# harp_expander_magnetic_encoder_v1_0.net
KiCad netlist of a schematic drawn in EAGLE
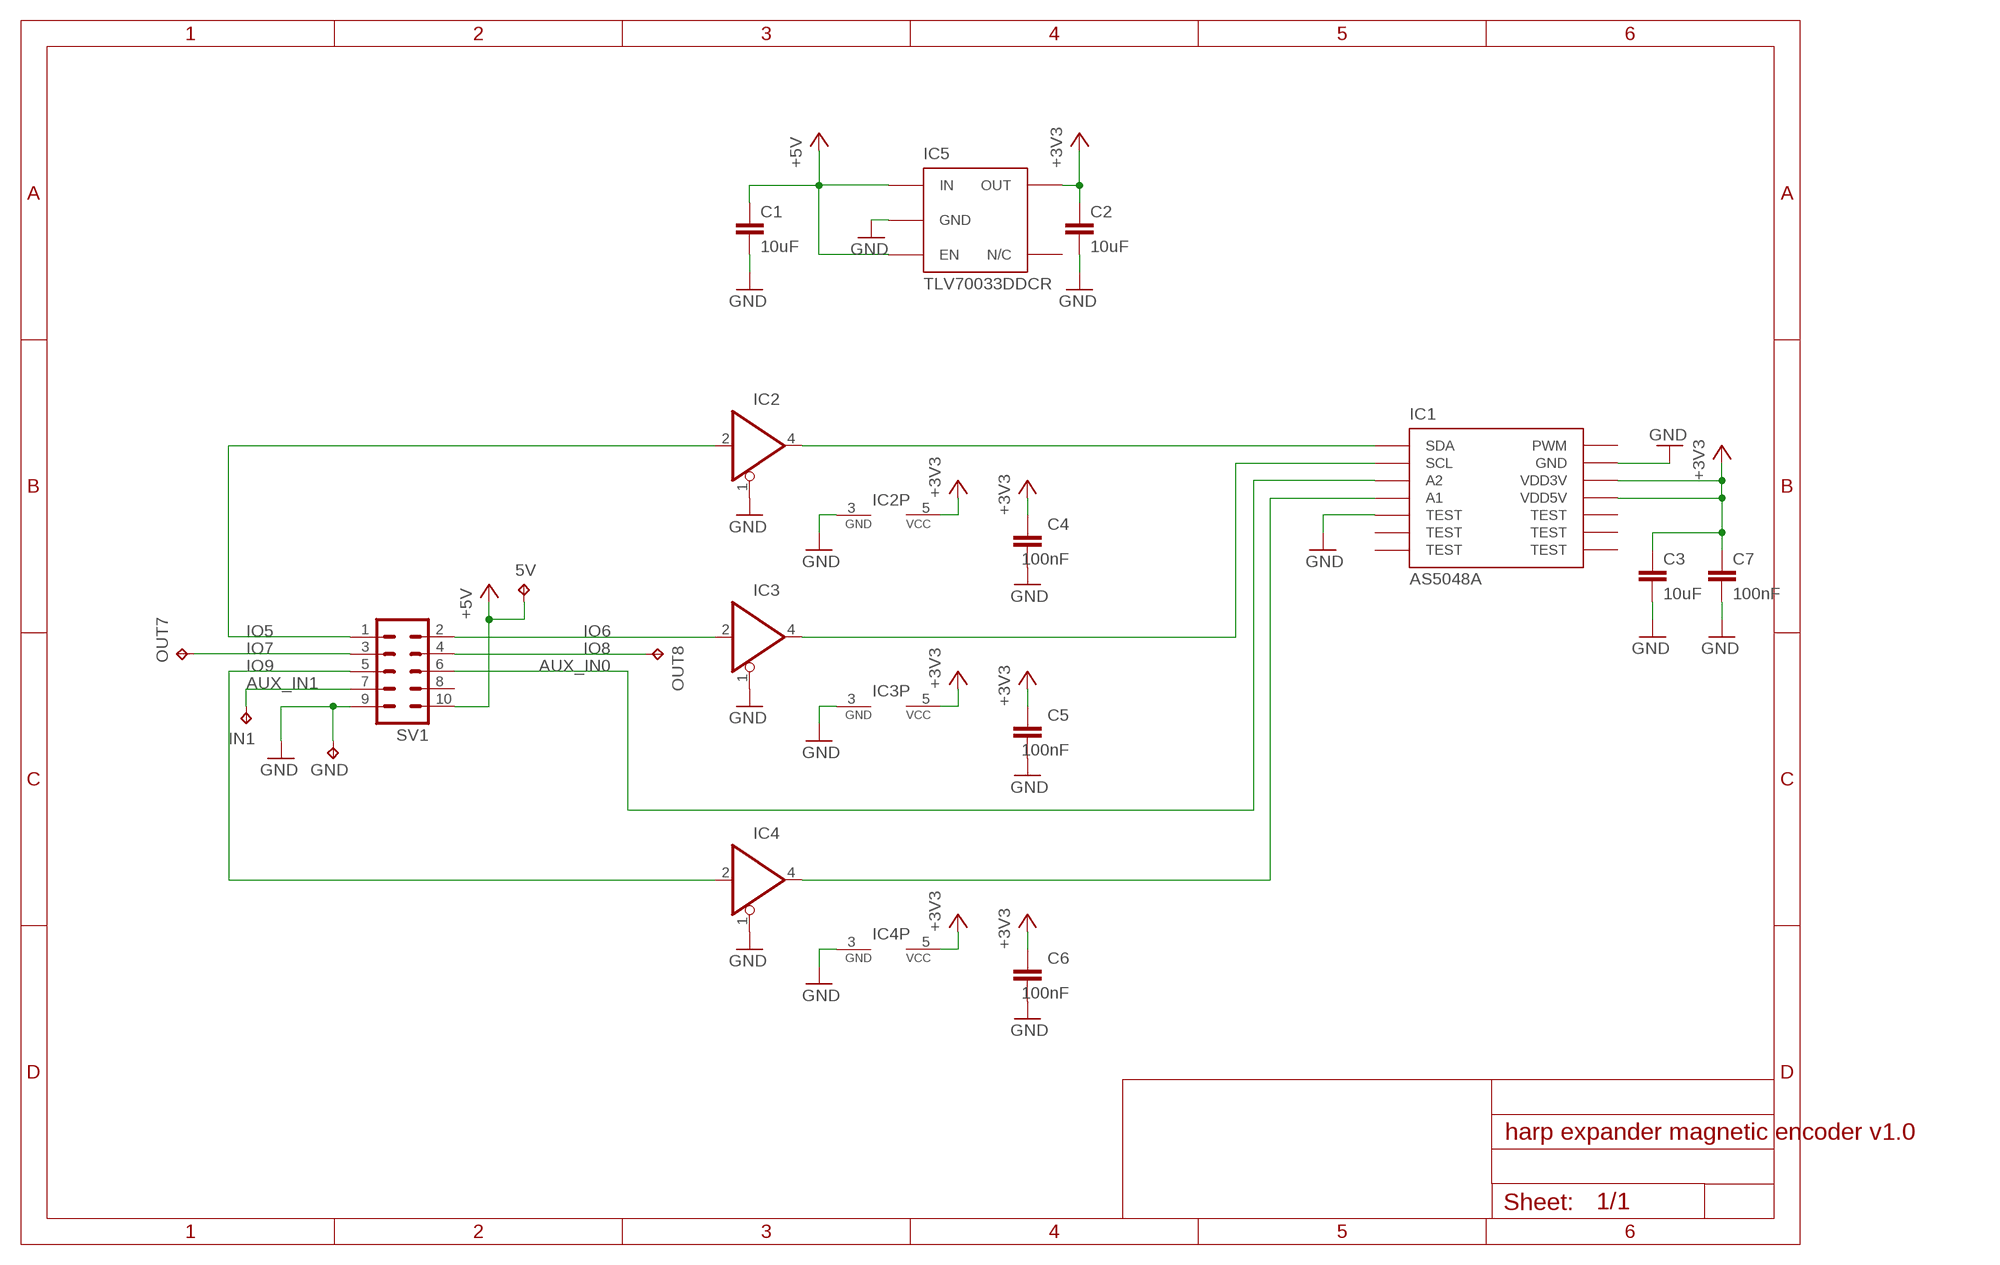
[diagram p0: schematic, sheet 1]

(export (version "E")
  (design (tool "Eeschema 10.0.6"))
  (components
    (comp (ref "5V")
      (value "TPPAD1-13")
      (footprint "eagle-import:P1-13")
      (libsource (lib "eagle-import") (part "TPPAD1-13"))
    )
    (comp (ref "C1")
      (value "10uF")
      (footprint "eagle-import:C0603")
      (fields (field (name "MPN") "C1608X6S1C475K080AC"))
      (libsource (lib "eagle-import") (part "C-EUC0603"))
    )
    (comp (ref "C2")
      (value "10uF")
      (footprint "eagle-import:C0603")
      (fields (field (name "MPN") "C1608X6S1C475K080AC"))
      (libsource (lib "eagle-import") (part "C-EUC0603"))
    )
    (comp (ref "C3")
      (value "10uF")
      (footprint "eagle-import:C0603")
      (fields (field (name "MPN") "C1608X6S1C475K080AC"))
      (libsource (lib "eagle-import") (part "C-EUC0603"))
    )
    (comp (ref "C4")
      (value "100nF")
      (footprint "eagle-import:C0402")
      (fields (field (name "MPN") "MC0402B104K160CT"))
      (libsource (lib "eagle-import") (part "C-EUC0402"))
    )
    (comp (ref "C5")
      (value "100nF")
      (footprint "eagle-import:C0402")
      (fields (field (name "MPN") "MC0402B104K160CT"))
      (libsource (lib "eagle-import") (part "C-EUC0402"))
    )
    (comp (ref "C6")
      (value "100nF")
      (footprint "eagle-import:C0402")
      (fields (field (name "MPN") "MC0402B104K160CT"))
      (libsource (lib "eagle-import") (part "C-EUC0402"))
    )
    (comp (ref "C7")
      (value "100nF")
      (footprint "eagle-import:C0402")
      (fields (field (name "MPN") "MC0402B104K160CT"))
      (libsource (lib "eagle-import") (part "C-EUC0402"))
    )
    (comp (ref "GND")
      (value "TPPAD1-13")
      (footprint "eagle-import:P1-13")
      (libsource (lib "eagle-import") (part "TPPAD1-13"))
    )
    (comp (ref "IC1")
      (value "AS5048A")
      (footprint "eagle-import:TSSOP-14")
      (libsource (lib "eagle-import") (part "AS5048B"))
    )
    (comp (ref "IC2")
      (value "SN74LVC1G125DBVT")
      (footprint "eagle-import:SOT23-5")
      (fields (field (name "MPN") "SN74LVC1G125DBVT"))
      (libsource (lib "eagle-import") (part "741G125DBVAHC"))
    )
    (comp (ref "IC3")
      (value "SN74LVC1G125DBVT")
      (footprint "eagle-import:SOT23-5")
      (fields (field (name "MPN") "SN74LVC1G125DBVT"))
      (libsource (lib "eagle-import") (part "741G125DBVAHC"))
    )
    (comp (ref "IC4")
      (value "SN74LVC1G125DBVT")
      (footprint "eagle-import:SOT23-5")
      (fields (field (name "MPN") "SN74LVC1G125DBVT"))
      (libsource (lib "eagle-import") (part "741G125DBVAHC"))
    )
    (comp (ref "IC5")
      (value "TLV70033DDCR")
      (footprint "eagle-import:TSOT23-5")
      (libsource (lib "eagle-import") (part "TLV700XX"))
    )
    (comp (ref "IN1")
      (value "TPPAD1-13")
      (footprint "eagle-import:P1-13")
      (libsource (lib "eagle-import") (part "TPPAD1-13"))
    )
    (comp (ref "OUT7")
      (value "TPPAD1-13")
      (footprint "eagle-import:P1-13")
      (libsource (lib "eagle-import") (part "TPPAD1-13"))
    )
    (comp (ref "OUT8")
      (value "TPPAD1-13")
      (footprint "eagle-import:P1-13")
      (libsource (lib "eagle-import") (part "TPPAD1-13"))
    )
    (comp (ref "SV1")
      (value "ML10")
      (footprint "eagle-import:ML10")
      (libsource (lib "eagle-import") (part "ML10"))
    )
  )
  (nets
    (net (code "1") (name "+3V3") (class "Default")
      (node (ref "C2") (pin "1") (pinfunction "1_1") (pintype "passive"))
      (node (ref "C3") (pin "1") (pinfunction "1_1") (pintype "passive"))
      (node (ref "C4") (pin "1") (pinfunction "1_1") (pintype "passive"))
      (node (ref "C5") (pin "1") (pinfunction "1_1") (pintype "passive"))
      (node (ref "C6") (pin "1") (pinfunction "1_1") (pintype "passive"))
      (node (ref "C7") (pin "1") (pinfunction "1_1") (pintype "passive"))
      (node (ref "IC1") (pin "11") (pinfunction "VDD5V_11") (pintype "bidirectional"))
      (node (ref "IC1") (pin "12") (pinfunction "VDD3V_12") (pintype "bidirectional"))
      (node (ref "IC2") (pin "5") (pinfunction "VCC_5") (pintype "power_in"))
      (node (ref "IC3") (pin "5") (pinfunction "VCC_5") (pintype "power_in"))
      (node (ref "IC4") (pin "5") (pinfunction "VCC_5") (pintype "power_in"))
      (node (ref "IC5") (pin "5") (pinfunction "OUT_5") (pintype "bidirectional"))
    )
    (net (code "2") (name "+5V") (class "Default")
      (node (ref "5V") (pin "TP") (pinfunction "TP_TP") (pintype "input"))
      (node (ref "C1") (pin "1") (pinfunction "1_1") (pintype "passive"))
      (node (ref "IC5") (pin "1") (pinfunction "IN_1") (pintype "bidirectional"))
      (node (ref "IC5") (pin "3") (pinfunction "EN_3") (pintype "bidirectional"))
      (node (ref "SV1") (pin "10") (pinfunction "10_10") (pintype "passive"))
    )
    (net (code "3") (name "/AUX_IN0") (class "Default")
      (node (ref "IC1") (pin "3") (pinfunction "A2_3") (pintype "bidirectional"))
      (node (ref "SV1") (pin "6") (pinfunction "6_6") (pintype "passive"))
    )
    (net (code "4") (name "/AUX_IN1") (class "Default")
      (node (ref "IN1") (pin "TP") (pinfunction "TP_TP") (pintype "input"))
      (node (ref "SV1") (pin "7") (pinfunction "7_7") (pintype "passive"))
    )
    (net (code "5") (name "/IO5") (class "Default")
      (node (ref "IC2") (pin "2") (pinfunction "I_2") (pintype "input"))
      (node (ref "SV1") (pin "1") (pinfunction "1_1") (pintype "passive"))
    )
    (net (code "6") (name "/IO6") (class "Default")
      (node (ref "IC3") (pin "2") (pinfunction "I_2") (pintype "input"))
      (node (ref "SV1") (pin "2") (pinfunction "2_2") (pintype "passive"))
    )
    (net (code "7") (name "/IO7") (class "Default")
      (node (ref "OUT7") (pin "TP") (pinfunction "TP_TP") (pintype "input"))
      (node (ref "SV1") (pin "3") (pinfunction "3_3") (pintype "passive"))
    )
    (net (code "8") (name "/IO8") (class "Default")
      (node (ref "OUT8") (pin "TP") (pinfunction "TP_TP") (pintype "input"))
      (node (ref "SV1") (pin "4") (pinfunction "4_4") (pintype "passive"))
    )
    (net (code "9") (name "/IO9") (class "Default")
      (node (ref "IC4") (pin "2") (pinfunction "I_2") (pintype "input"))
      (node (ref "SV1") (pin "5") (pinfunction "5_5") (pintype "passive"))
    )
    (net (code "10") (name "GND") (class "Default")
      (node (ref "C1") (pin "2") (pinfunction "2_2") (pintype "passive"))
      (node (ref "C2") (pin "2") (pinfunction "2_2") (pintype "passive"))
      (node (ref "C3") (pin "2") (pinfunction "2_2") (pintype "passive"))
      (node (ref "C4") (pin "2") (pinfunction "2_2") (pintype "passive"))
      (node (ref "C5") (pin "2") (pinfunction "2_2") (pintype "passive"))
      (node (ref "C6") (pin "2") (pinfunction "2_2") (pintype "passive"))
      (node (ref "C7") (pin "2") (pinfunction "2_2") (pintype "passive"))
      (node (ref "GND") (pin "TP") (pinfunction "TP_TP") (pintype "input"))
      (node (ref "IC1") (pin "13") (pinfunction "GND_13") (pintype "bidirectional"))
      (node (ref "IC1") (pin "5") (pinfunction "TEST_5") (pintype "bidirectional"))
      (node (ref "IC2") (pin "1") (pinfunction "OE_1") (pintype "input"))
      (node (ref "IC2") (pin "3") (pinfunction "GND_3") (pintype "power_in"))
      (node (ref "IC3") (pin "1") (pinfunction "OE_1") (pintype "input"))
      (node (ref "IC3") (pin "3") (pinfunction "GND_3") (pintype "power_in"))
      (node (ref "IC4") (pin "1") (pinfunction "OE_1") (pintype "input"))
      (node (ref "IC4") (pin "3") (pinfunction "GND_3") (pintype "power_in"))
      (node (ref "IC5") (pin "2") (pinfunction "GND_2") (pintype "bidirectional"))
      (node (ref "SV1") (pin "9") (pinfunction "9_9") (pintype "passive"))
    )
    (net (code "11") (name "Net-(IC1-A1)") (class "Default")
      (node (ref "IC1") (pin "4") (pinfunction "A1_4") (pintype "bidirectional"))
      (node (ref "IC4") (pin "4") (pinfunction "O_4") (pintype "tri_state"))
    )
    (net (code "12") (name "Net-(IC1-SCL)") (class "Default")
      (node (ref "IC1") (pin "2") (pinfunction "SCL_2") (pintype "bidirectional"))
      (node (ref "IC3") (pin "4") (pinfunction "O_4") (pintype "tri_state"))
    )
    (net (code "13") (name "Net-(IC1-SDA)") (class "Default")
      (node (ref "IC1") (pin "1") (pinfunction "SDA_1") (pintype "bidirectional"))
      (node (ref "IC2") (pin "4") (pinfunction "O_4") (pintype "tri_state"))
    )
    (net (code "14") (name "unconnected-(IC1-PWM-Pad14)") (class "Default")
      (node (ref "IC1") (pin "14") (pinfunction "PWM_14") (pintype "bidirectional"))
    )
    (net (code "15") (name "unconnected-(IC1-TEST-Pad6)") (class "Default")
      (node (ref "IC1") (pin "6") (pinfunction "TEST_6") (pintype "bidirectional"))
    )
    (net (code "16") (name "unconnected-(IC1-TEST-Pad7)") (class "Default")
      (node (ref "IC1") (pin "7") (pinfunction "TEST_7") (pintype "bidirectional"))
    )
    (net (code "17") (name "unconnected-(IC1-TEST-Pad8)") (class "Default")
      (node (ref "IC1") (pin "8") (pinfunction "TEST_8") (pintype "bidirectional"))
    )
    (net (code "18") (name "unconnected-(IC1-TEST-Pad9)") (class "Default")
      (node (ref "IC1") (pin "9") (pinfunction "TEST_9") (pintype "bidirectional"))
    )
    (net (code "19") (name "unconnected-(IC1-TEST-Pad10)") (class "Default")
      (node (ref "IC1") (pin "10") (pinfunction "TEST_10") (pintype "bidirectional"))
    )
    (net (code "20") (name "unconnected-(IC5-N{slash}C-Pad4)") (class "Default")
      (node (ref "IC5") (pin "4") (pinfunction "N/C_4") (pintype "bidirectional"))
    )
    (net (code "21") (name "unconnected-(SV1-Pad8)") (class "Default")
      (node (ref "SV1") (pin "8") (pinfunction "8_8") (pintype "passive"))
    )
  )
)
